# ESC-simple_V2A.net
KiCad netlist of a schematic drawn in EAGLE
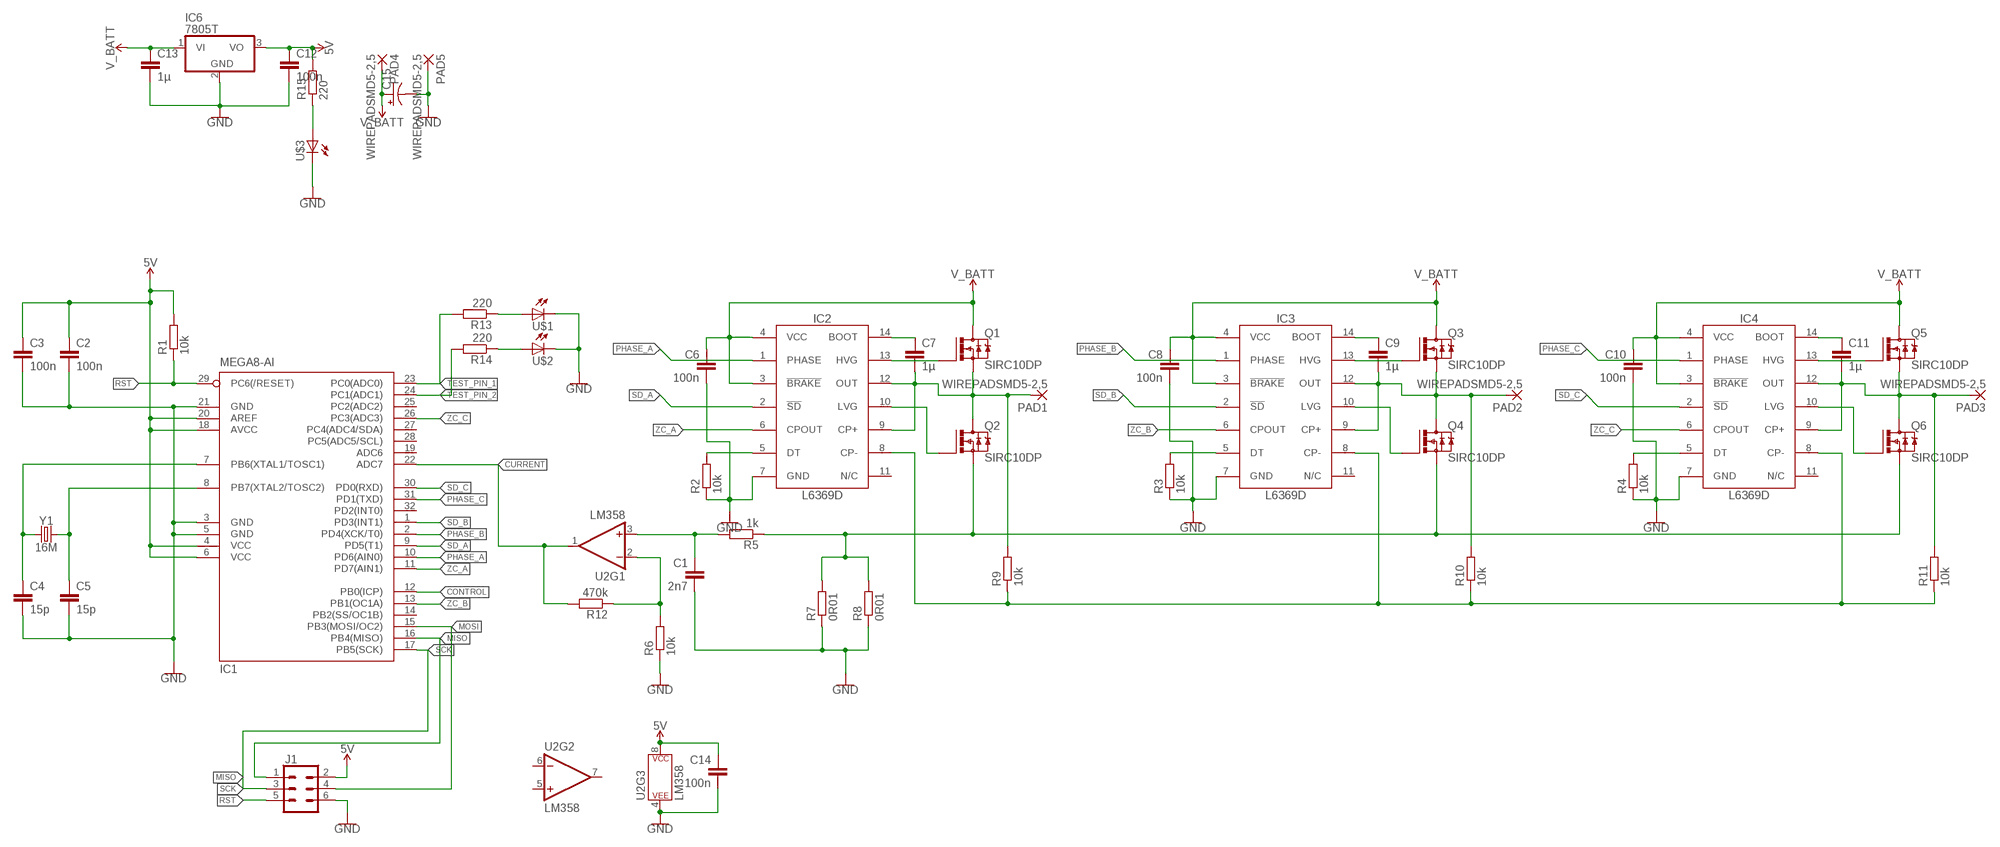
[diagram p0: schematic, sheet 1]

(export (version "E")
  (design (tool "Eeschema 10.0.6"))
  (components
    (comp (ref "C1")
      (value "2n7")
      (footprint "eagle-import:C1206K")
      (libsource (lib "eagle-import") (part "C-EUC1206K"))
    )
    (comp (ref "C2")
      (value "100n")
      (footprint "eagle-import:C1206K")
      (libsource (lib "eagle-import") (part "C-EUC1206K"))
    )
    (comp (ref "C3")
      (value "100n")
      (footprint "eagle-import:C1206K")
      (libsource (lib "eagle-import") (part "C-EUC1206K"))
    )
    (comp (ref "C4")
      (value "15p")
      (footprint "eagle-import:C1206K")
      (libsource (lib "eagle-import") (part "C-EUC1206K"))
    )
    (comp (ref "C5")
      (value "15p")
      (footprint "eagle-import:C1206K")
      (libsource (lib "eagle-import") (part "C-EUC1206K"))
    )
    (comp (ref "C6")
      (value "100n")
      (footprint "eagle-import:C1206K")
      (libsource (lib "eagle-import") (part "C-EUC1206K"))
    )
    (comp (ref "C7")
      (value "1µ")
      (footprint "eagle-import:C1206K")
      (libsource (lib "eagle-import") (part "C-EUC1206K"))
    )
    (comp (ref "C8")
      (value "100n")
      (footprint "eagle-import:C1206K")
      (libsource (lib "eagle-import") (part "C-EUC1206K"))
    )
    (comp (ref "C9")
      (value "1µ")
      (footprint "eagle-import:C1206K")
      (libsource (lib "eagle-import") (part "C-EUC1206K"))
    )
    (comp (ref "C10")
      (value "100n")
      (footprint "eagle-import:C1206K")
      (libsource (lib "eagle-import") (part "C-EUC1206K"))
    )
    (comp (ref "C11")
      (value "1µ")
      (footprint "eagle-import:C1206K")
      (libsource (lib "eagle-import") (part "C-EUC1206K"))
    )
    (comp (ref "C12")
      (value "100n")
      (footprint "eagle-import:C1206K")
      (libsource (lib "eagle-import") (part "C-EUC1206K"))
    )
    (comp (ref "C13")
      (value "1µ")
      (footprint "eagle-import:C1206K")
      (libsource (lib "eagle-import") (part "C-EUC1206K"))
    )
    (comp (ref "C14")
      (value "100n")
      (footprint "eagle-import:C1206K")
      (libsource (lib "eagle-import") (part "C-EUC1206K"))
    )
    (comp (ref "C15")
      (value "CPOL-USE5-13")
      (footprint "eagle-import:E5-13")
      (libsource (lib "eagle-import") (part "CPOL-USE5-13"))
    )
    (comp (ref "IC1")
      (value "MEGA8-AI")
      (footprint "eagle-import:TQFP32-08")
      (fields (field (name "MPN") "ATMEGA8-16AU"))
      (libsource (lib "eagle-import") (part "MEGA8-AI"))
    )
    (comp (ref "IC2")
      (value "L6369D")
      (footprint "eagle-import:SO-14")
      (libsource (lib "eagle-import") (part "L6369D"))
    )
    (comp (ref "IC3")
      (value "L6369D")
      (footprint "eagle-import:SO-14")
      (libsource (lib "eagle-import") (part "L6369D"))
    )
    (comp (ref "IC4")
      (value "L6369D")
      (footprint "eagle-import:SO-14")
      (libsource (lib "eagle-import") (part "L6369D"))
    )
    (comp (ref "IC6")
      (value "7805T")
      (footprint "eagle-import:TO220H")
      (libsource (lib "eagle-import") (part "78T05"))
    )
    (comp (ref "J1")
      (value "CONN_03X22X3_SILK_MALE_PTH")
      (footprint "eagle-import:2X3")
      (libsource (lib "eagle-import") (part "CONN_03X22X3_SILK_MALE_PTH"))
    )
    (comp (ref "PAD1")
      (value "WIREPADSMD5-2,5")
      (footprint "eagle-import:5-2,5")
      (libsource (lib "eagle-import") (part "WIREPADSMD5-2,5"))
    )
    (comp (ref "PAD2")
      (value "WIREPADSMD5-2,5")
      (footprint "eagle-import:5-2,5")
      (libsource (lib "eagle-import") (part "WIREPADSMD5-2,5"))
    )
    (comp (ref "PAD3")
      (value "WIREPADSMD5-2,5")
      (footprint "eagle-import:5-2,5")
      (libsource (lib "eagle-import") (part "WIREPADSMD5-2,5"))
    )
    (comp (ref "PAD4")
      (value "WIREPADSMD5-2,5")
      (footprint "eagle-import:5-2,5")
      (libsource (lib "eagle-import") (part "WIREPADSMD5-2,5"))
    )
    (comp (ref "PAD5")
      (value "WIREPADSMD5-2,5")
      (footprint "eagle-import:5-2,5")
      (libsource (lib "eagle-import") (part "WIREPADSMD5-2,5"))
    )
    (comp (ref "Q1")
      (value "SIRC10DP")
      (footprint "eagle-import:POWERPAK_SO-8_SINGLE")
      (libsource (lib "eagle-import") (part "SIRC10DP"))
    )
    (comp (ref "Q2")
      (value "SIRC10DP")
      (footprint "eagle-import:POWERPAK_SO-8_SINGLE")
      (libsource (lib "eagle-import") (part "SIRC10DP"))
    )
    (comp (ref "Q3")
      (value "SIRC10DP")
      (footprint "eagle-import:POWERPAK_SO-8_SINGLE")
      (libsource (lib "eagle-import") (part "SIRC10DP"))
    )
    (comp (ref "Q4")
      (value "SIRC10DP")
      (footprint "eagle-import:POWERPAK_SO-8_SINGLE")
      (libsource (lib "eagle-import") (part "SIRC10DP"))
    )
    (comp (ref "Q5")
      (value "SIRC10DP")
      (footprint "eagle-import:POWERPAK_SO-8_SINGLE")
      (libsource (lib "eagle-import") (part "SIRC10DP"))
    )
    (comp (ref "Q6")
      (value "SIRC10DP")
      (footprint "eagle-import:POWERPAK_SO-8_SINGLE")
      (libsource (lib "eagle-import") (part "SIRC10DP"))
    )
    (comp (ref "R1")
      (value "10k")
      (footprint "eagle-import:R1206")
      (libsource (lib "eagle-import") (part "R-EU_R1206"))
    )
    (comp (ref "R2")
      (value "10k")
      (footprint "eagle-import:R1206")
      (libsource (lib "eagle-import") (part "R-EU_R1206"))
    )
    (comp (ref "R3")
      (value "10k")
      (footprint "eagle-import:R1206")
      (libsource (lib "eagle-import") (part "R-EU_R1206"))
    )
    (comp (ref "R4")
      (value "10k")
      (footprint "eagle-import:R1206")
      (libsource (lib "eagle-import") (part "R-EU_R1206"))
    )
    (comp (ref "R5")
      (value "1k")
      (footprint "eagle-import:R1206")
      (libsource (lib "eagle-import") (part "R-EU_R1206"))
    )
    (comp (ref "R6")
      (value "10k")
      (footprint "eagle-import:R1206")
      (libsource (lib "eagle-import") (part "R-EU_R1206"))
    )
    (comp (ref "R7")
      (value "0R01")
      (footprint "eagle-import:R1206")
      (libsource (lib "eagle-import") (part "R-EU_R1206"))
    )
    (comp (ref "R8")
      (value "0R01")
      (footprint "eagle-import:R1206")
      (libsource (lib "eagle-import") (part "R-EU_R1206"))
    )
    (comp (ref "R9")
      (value "10k")
      (footprint "eagle-import:R1206")
      (libsource (lib "eagle-import") (part "R-EU_R1206"))
    )
    (comp (ref "R10")
      (value "10k")
      (footprint "eagle-import:R1206")
      (libsource (lib "eagle-import") (part "R-EU_R1206"))
    )
    (comp (ref "R11")
      (value "10k")
      (footprint "eagle-import:R1206")
      (libsource (lib "eagle-import") (part "R-EU_R1206"))
    )
    (comp (ref "R12")
      (value "470k")
      (footprint "eagle-import:R1206")
      (libsource (lib "eagle-import") (part "R-EU_R1206"))
    )
    (comp (ref "R13")
      (value "220")
      (footprint "eagle-import:R1206")
      (libsource (lib "eagle-import") (part "R-EU_R1206"))
    )
    (comp (ref "R14")
      (value "220")
      (footprint "eagle-import:R1206")
      (libsource (lib "eagle-import") (part "R-EU_R1206"))
    )
    (comp (ref "R15")
      (value "220")
      (footprint "eagle-import:R1206")
      (libsource (lib "eagle-import") (part "R-EU_R1206"))
    )
    (comp (ref "U$1")
      (value "LED")
      (footprint "eagle-import:3MM_LED")
      (libsource (lib "eagle-import") (part "LED"))
    )
    (comp (ref "U$2")
      (value "LED")
      (footprint "eagle-import:3MM_LED")
      (libsource (lib "eagle-import") (part "LED"))
    )
    (comp (ref "U$3")
      (value "LED")
      (footprint "eagle-import:3MM_LED")
      (libsource (lib "eagle-import") (part "LED"))
    )
    (comp (ref "U2")
      (value "LM358")
      (footprint "eagle-import:DIP08")
      (libsource (lib "eagle-import") (part "LM358"))
    )
    (comp (ref "Y1")
      (value "16M")
      (footprint "eagle-import:HC49UP")
      (libsource (lib "eagle-import") (part "CRYSTALSMD-HC49UP"))
    )
  )
  (nets
    (net (code "1") (name "5V") (class "Default")
      (node (ref "C12") (pin "1") (pinfunction "1_1") (pintype "passive"))
      (node (ref "C14") (pin "1") (pinfunction "1_1") (pintype "passive"))
      (node (ref "C2") (pin "1") (pinfunction "1_1") (pintype "passive"))
      (node (ref "C3") (pin "1") (pinfunction "1_1") (pintype "passive"))
      (node (ref "IC1") (pin "18") (pinfunction "AVCC_18") (pintype "power_in"))
      (node (ref "IC1") (pin "20") (pinfunction "AREF_20") (pintype "passive"))
      (node (ref "IC1") (pin "4") (pinfunction "VCC_4") (pintype "power_in"))
      (node (ref "IC1") (pin "6") (pinfunction "VCC_6") (pintype "power_in"))
      (node (ref "IC6") (pin "3") (pinfunction "VO_3") (pintype "passive"))
      (node (ref "J1") (pin "2") (pinfunction "2_2") (pintype "bidirectional"))
      (node (ref "R1") (pin "2") (pinfunction "2_2") (pintype "passive"))
      (node (ref "R15") (pin "2") (pinfunction "2_2") (pintype "passive"))
      (node (ref "U2") (pin "8") (pinfunction "P$V+_8") (pintype "bidirectional"))
    )
    (net (code "2") (name "CONTROL") (class "Default")
      (node (ref "IC1") (pin "12") (pinfunction "PB0(ICP)_12") (pintype "bidirectional"))
    )
    (net (code "3") (name "CURRENT") (class "Default")
      (node (ref "IC1") (pin "22") (pinfunction "ADC7_22") (pintype "bidirectional"))
      (node (ref "R12") (pin "2") (pinfunction "2_2") (pintype "passive"))
      (node (ref "U2") (pin "1") (pinfunction "OUT_1") (pintype "output"))
    )
    (net (code "4") (name "GND") (class "Default")
      (node (ref "C1") (pin "2") (pinfunction "2_2") (pintype "passive"))
      (node (ref "C10") (pin "2") (pinfunction "2_2") (pintype "passive"))
      (node (ref "C12") (pin "2") (pinfunction "2_2") (pintype "passive"))
      (node (ref "C13") (pin "2") (pinfunction "2_2") (pintype "passive"))
      (node (ref "C14") (pin "2") (pinfunction "2_2") (pintype "passive"))
      (node (ref "C15") (pin "-") (pinfunction "-_-") (pintype "passive"))
      (node (ref "C2") (pin "2") (pinfunction "2_2") (pintype "passive"))
      (node (ref "C3") (pin "2") (pinfunction "2_2") (pintype "passive"))
      (node (ref "C4") (pin "2") (pinfunction "2_2") (pintype "passive"))
      (node (ref "C5") (pin "2") (pinfunction "2_2") (pintype "passive"))
      (node (ref "C6") (pin "2") (pinfunction "2_2") (pintype "passive"))
      (node (ref "C8") (pin "2") (pinfunction "2_2") (pintype "passive"))
      (node (ref "IC1") (pin "21") (pinfunction "GND_21") (pintype "power_in"))
      (node (ref "IC1") (pin "3") (pinfunction "GND_3") (pintype "power_in"))
      (node (ref "IC1") (pin "5") (pinfunction "GND_5") (pintype "power_in"))
      (node (ref "IC2") (pin "7") (pinfunction "GND_7") (pintype "power_in"))
      (node (ref "IC3") (pin "7") (pinfunction "GND_7") (pintype "power_in"))
      (node (ref "IC4") (pin "7") (pinfunction "GND_7") (pintype "power_in"))
      (node (ref "IC6") (pin "2") (pinfunction "GND_2") (pintype "passive"))
      (node (ref "J1") (pin "6") (pinfunction "6_6") (pintype "bidirectional"))
      (node (ref "PAD5") (pin "1") (pinfunction "P_1") (pintype "passive"))
      (node (ref "R2") (pin "1") (pinfunction "1_1") (pintype "passive"))
      (node (ref "R3") (pin "1") (pinfunction "1_1") (pintype "passive"))
      (node (ref "R4") (pin "1") (pinfunction "1_1") (pintype "passive"))
      (node (ref "R6") (pin "1") (pinfunction "1_1") (pintype "passive"))
      (node (ref "R7") (pin "1") (pinfunction "1_1") (pintype "passive"))
      (node (ref "R8") (pin "1") (pinfunction "1_1") (pintype "passive"))
      (node (ref "U$1") (pin "C") (pinfunction "C_C") (pintype "passive"))
      (node (ref "U$2") (pin "C") (pinfunction "C_C") (pintype "passive"))
      (node (ref "U$3") (pin "C") (pinfunction "C_C") (pintype "passive"))
      (node (ref "U2") (pin "4") (pinfunction "P$V-_4") (pintype "bidirectional"))
    )
    (net (code "5") (name "MISO") (class "Default")
      (node (ref "IC1") (pin "16") (pinfunction "PB4(MISO)_16") (pintype "bidirectional"))
      (node (ref "J1") (pin "1") (pinfunction "1_1") (pintype "bidirectional"))
    )
    (net (code "6") (name "MOSI") (class "Default")
      (node (ref "IC1") (pin "15") (pinfunction "PB3(MOSI/OC2)_15") (pintype "bidirectional"))
      (node (ref "J1") (pin "4") (pinfunction "4_4") (pintype "bidirectional"))
    )
    (net (code "7") (name "Net-(IC1-PB6(XTAL1{slash}TOSC1))") (class "Default")
      (node (ref "C4") (pin "1") (pinfunction "1_1") (pintype "passive"))
      (node (ref "IC1") (pin "7") (pinfunction "PB6(XTAL1/TOSC1)_7") (pintype "bidirectional"))
      (node (ref "Y1") (pin "1") (pinfunction "1_1") (pintype "passive"))
    )
    (net (code "8") (name "Net-(IC1-PB7(XTAL2{slash}TOSC2))") (class "Default")
      (node (ref "C5") (pin "1") (pinfunction "1_1") (pintype "passive"))
      (node (ref "IC1") (pin "8") (pinfunction "PB7(XTAL2/TOSC2)_8") (pintype "bidirectional"))
      (node (ref "Y1") (pin "2") (pinfunction "2_2") (pintype "passive"))
    )
    (net (code "9") (name "Net-(IC2-BOOT)") (class "Default")
      (node (ref "C7") (pin "1") (pinfunction "1_1") (pintype "passive"))
      (node (ref "IC2") (pin "14") (pinfunction "BOOT_14") (pintype "power_in"))
    )
    (net (code "10") (name "Net-(IC2-CP+)") (class "Default")
      (node (ref "C7") (pin "2") (pinfunction "2_2") (pintype "passive"))
      (node (ref "IC2") (pin "12") (pinfunction "OUT_12") (pintype "output"))
      (node (ref "IC2") (pin "9") (pinfunction "CP+_9") (pintype "input"))
      (node (ref "PAD1") (pin "1") (pinfunction "P_1") (pintype "passive"))
      (node (ref "Q1") (pin "1") (pinfunction "S_1") (pintype "bidirectional"))
      (node (ref "Q1") (pin "2") (pinfunction "S_2") (pintype "bidirectional"))
      (node (ref "Q1") (pin "3") (pinfunction "S_3") (pintype "bidirectional"))
      (node (ref "Q2") (pin "5") (pinfunction "D_5") (pintype "bidirectional"))
      (node (ref "Q2") (pin "6") (pinfunction "D_6") (pintype "bidirectional"))
      (node (ref "Q2") (pin "7") (pinfunction "D_7") (pintype "bidirectional"))
      (node (ref "Q2") (pin "8") (pinfunction "D_8") (pintype "bidirectional"))
      (node (ref "Q2") (pin "9") (pinfunction "D_9") (pintype "bidirectional"))
      (node (ref "R9") (pin "2") (pinfunction "2_2") (pintype "passive"))
    )
    (net (code "11") (name "Net-(IC2-CP-)") (class "Default")
      (node (ref "IC2") (pin "8") (pinfunction "CP-_8") (pintype "input"))
      (node (ref "IC3") (pin "8") (pinfunction "CP-_8") (pintype "input"))
      (node (ref "IC4") (pin "8") (pinfunction "CP-_8") (pintype "input"))
      (node (ref "R10") (pin "1") (pinfunction "1_1") (pintype "passive"))
      (node (ref "R11") (pin "1") (pinfunction "1_1") (pintype "passive"))
      (node (ref "R9") (pin "1") (pinfunction "1_1") (pintype "passive"))
    )
    (net (code "12") (name "Net-(IC2-DT)") (class "Default")
      (node (ref "IC2") (pin "5") (pinfunction "DT_5") (pintype "input"))
      (node (ref "R2") (pin "2") (pinfunction "2_2") (pintype "passive"))
    )
    (net (code "13") (name "Net-(IC2-HVG)") (class "Default")
      (node (ref "IC2") (pin "13") (pinfunction "HVG_13") (pintype "output"))
      (node (ref "Q1") (pin "4") (pinfunction "G_4") (pintype "bidirectional"))
    )
    (net (code "14") (name "Net-(IC2-LVG)") (class "Default")
      (node (ref "IC2") (pin "10") (pinfunction "LVG_10") (pintype "output"))
      (node (ref "Q2") (pin "4") (pinfunction "G_4") (pintype "bidirectional"))
    )
    (net (code "15") (name "Net-(IC3-BOOT)") (class "Default")
      (node (ref "C9") (pin "1") (pinfunction "1_1") (pintype "passive"))
      (node (ref "IC3") (pin "14") (pinfunction "BOOT_14") (pintype "power_in"))
    )
    (net (code "16") (name "Net-(IC3-CP+)") (class "Default")
      (node (ref "C9") (pin "2") (pinfunction "2_2") (pintype "passive"))
      (node (ref "IC3") (pin "12") (pinfunction "OUT_12") (pintype "output"))
      (node (ref "IC3") (pin "9") (pinfunction "CP+_9") (pintype "input"))
      (node (ref "PAD2") (pin "1") (pinfunction "P_1") (pintype "passive"))
      (node (ref "Q3") (pin "1") (pinfunction "S_1") (pintype "bidirectional"))
      (node (ref "Q3") (pin "2") (pinfunction "S_2") (pintype "bidirectional"))
      (node (ref "Q3") (pin "3") (pinfunction "S_3") (pintype "bidirectional"))
      (node (ref "Q4") (pin "5") (pinfunction "D_5") (pintype "bidirectional"))
      (node (ref "Q4") (pin "6") (pinfunction "D_6") (pintype "bidirectional"))
      (node (ref "Q4") (pin "7") (pinfunction "D_7") (pintype "bidirectional"))
      (node (ref "Q4") (pin "8") (pinfunction "D_8") (pintype "bidirectional"))
      (node (ref "Q4") (pin "9") (pinfunction "D_9") (pintype "bidirectional"))
      (node (ref "R10") (pin "2") (pinfunction "2_2") (pintype "passive"))
    )
    (net (code "17") (name "Net-(IC3-DT)") (class "Default")
      (node (ref "IC3") (pin "5") (pinfunction "DT_5") (pintype "input"))
      (node (ref "R3") (pin "2") (pinfunction "2_2") (pintype "passive"))
    )
    (net (code "18") (name "Net-(IC3-HVG)") (class "Default")
      (node (ref "IC3") (pin "13") (pinfunction "HVG_13") (pintype "output"))
      (node (ref "Q3") (pin "4") (pinfunction "G_4") (pintype "bidirectional"))
    )
    (net (code "19") (name "Net-(IC3-LVG)") (class "Default")
      (node (ref "IC3") (pin "10") (pinfunction "LVG_10") (pintype "output"))
      (node (ref "Q4") (pin "4") (pinfunction "G_4") (pintype "bidirectional"))
    )
    (net (code "20") (name "Net-(IC4-BOOT)") (class "Default")
      (node (ref "C11") (pin "1") (pinfunction "1_1") (pintype "passive"))
      (node (ref "IC4") (pin "14") (pinfunction "BOOT_14") (pintype "power_in"))
    )
    (net (code "21") (name "Net-(IC4-CP+)") (class "Default")
      (node (ref "C11") (pin "2") (pinfunction "2_2") (pintype "passive"))
      (node (ref "IC4") (pin "12") (pinfunction "OUT_12") (pintype "output"))
      (node (ref "IC4") (pin "9") (pinfunction "CP+_9") (pintype "input"))
      (node (ref "PAD3") (pin "1") (pinfunction "P_1") (pintype "passive"))
      (node (ref "Q5") (pin "1") (pinfunction "S_1") (pintype "bidirectional"))
      (node (ref "Q5") (pin "2") (pinfunction "S_2") (pintype "bidirectional"))
      (node (ref "Q5") (pin "3") (pinfunction "S_3") (pintype "bidirectional"))
      (node (ref "Q6") (pin "5") (pinfunction "D_5") (pintype "bidirectional"))
      (node (ref "Q6") (pin "6") (pinfunction "D_6") (pintype "bidirectional"))
      (node (ref "Q6") (pin "7") (pinfunction "D_7") (pintype "bidirectional"))
      (node (ref "Q6") (pin "8") (pinfunction "D_8") (pintype "bidirectional"))
      (node (ref "Q6") (pin "9") (pinfunction "D_9") (pintype "bidirectional"))
      (node (ref "R11") (pin "2") (pinfunction "2_2") (pintype "passive"))
    )
    (net (code "22") (name "Net-(IC4-DT)") (class "Default")
      (node (ref "IC4") (pin "5") (pinfunction "DT_5") (pintype "input"))
      (node (ref "R4") (pin "2") (pinfunction "2_2") (pintype "passive"))
    )
    (net (code "23") (name "Net-(IC4-HVG)") (class "Default")
      (node (ref "IC4") (pin "13") (pinfunction "HVG_13") (pintype "output"))
      (node (ref "Q5") (pin "4") (pinfunction "G_4") (pintype "bidirectional"))
    )
    (net (code "24") (name "Net-(IC4-LVG)") (class "Default")
      (node (ref "IC4") (pin "10") (pinfunction "LVG_10") (pintype "output"))
      (node (ref "Q6") (pin "4") (pinfunction "G_4") (pintype "bidirectional"))
    )
    (net (code "25") (name "Net-(Q2-S-Pad1)") (class "Default")
      (node (ref "Q2") (pin "1") (pinfunction "S_1") (pintype "bidirectional"))
      (node (ref "Q2") (pin "2") (pinfunction "S_2") (pintype "bidirectional"))
      (node (ref "Q2") (pin "3") (pinfunction "S_3") (pintype "bidirectional"))
      (node (ref "Q4") (pin "1") (pinfunction "S_1") (pintype "bidirectional"))
      (node (ref "Q4") (pin "2") (pinfunction "S_2") (pintype "bidirectional"))
      (node (ref "Q4") (pin "3") (pinfunction "S_3") (pintype "bidirectional"))
      (node (ref "Q6") (pin "1") (pinfunction "S_1") (pintype "bidirectional"))
      (node (ref "Q6") (pin "2") (pinfunction "S_2") (pintype "bidirectional"))
      (node (ref "Q6") (pin "3") (pinfunction "S_3") (pintype "bidirectional"))
      (node (ref "R5") (pin "1") (pinfunction "1_1") (pintype "passive"))
      (node (ref "R7") (pin "2") (pinfunction "2_2") (pintype "passive"))
      (node (ref "R8") (pin "2") (pinfunction "2_2") (pintype "passive"))
    )
    (net (code "26") (name "Net-(R13-Pad1)") (class "Default")
      (node (ref "R13") (pin "1") (pinfunction "1_1") (pintype "passive"))
      (node (ref "U$1") (pin "A") (pinfunction "A_A") (pintype "passive"))
    )
    (net (code "27") (name "Net-(R14-Pad1)") (class "Default")
      (node (ref "R14") (pin "1") (pinfunction "1_1") (pintype "passive"))
      (node (ref "U$2") (pin "A") (pinfunction "A_A") (pintype "passive"))
    )
    (net (code "28") (name "Net-(R15-Pad1)") (class "Default")
      (node (ref "R15") (pin "1") (pinfunction "1_1") (pintype "passive"))
      (node (ref "U$3") (pin "A") (pinfunction "A_A") (pintype "passive"))
    )
    (net (code "29") (name "Net-(U2A-+IN)") (class "Default")
      (node (ref "C1") (pin "1") (pinfunction "1_1") (pintype "passive"))
      (node (ref "R5") (pin "2") (pinfunction "2_2") (pintype "passive"))
      (node (ref "U2") (pin "3") (pinfunction "+IN_3") (pintype "input"))
    )
    (net (code "30") (name "Net-(U2A--IN)") (class "Default")
      (node (ref "R12") (pin "1") (pinfunction "1_1") (pintype "passive"))
      (node (ref "R6") (pin "2") (pinfunction "2_2") (pintype "passive"))
      (node (ref "U2") (pin "2") (pinfunction "-IN_2") (pintype "input"))
    )
    (net (code "31") (name "PHASE_A") (class "Default")
      (node (ref "IC1") (pin "10") (pinfunction "PD6(AIN0)_10") (pintype "bidirectional"))
      (node (ref "IC2") (pin "1") (pinfunction "PHASE_1") (pintype "input"))
    )
    (net (code "32") (name "PHASE_B") (class "Default")
      (node (ref "IC1") (pin "2") (pinfunction "PD4(XCK/T0)_2") (pintype "bidirectional"))
      (node (ref "IC3") (pin "1") (pinfunction "PHASE_1") (pintype "input"))
    )
    (net (code "33") (name "PHASE_C") (class "Default")
      (node (ref "IC1") (pin "31") (pinfunction "PD1(TXD)_31") (pintype "bidirectional"))
      (node (ref "IC4") (pin "1") (pinfunction "PHASE_1") (pintype "input"))
    )
    (net (code "34") (name "RST") (class "Default")
      (node (ref "IC1") (pin "29") (pinfunction "PC6(/RESET)_29") (pintype "bidirectional"))
      (node (ref "J1") (pin "5") (pinfunction "5_5") (pintype "bidirectional"))
      (node (ref "R1") (pin "1") (pinfunction "1_1") (pintype "passive"))
    )
    (net (code "35") (name "SCK") (class "Default")
      (node (ref "IC1") (pin "17") (pinfunction "PB5(SCK)_17") (pintype "bidirectional"))
      (node (ref "J1") (pin "3") (pinfunction "3_3") (pintype "bidirectional"))
    )
    (net (code "36") (name "SD_A") (class "Default")
      (node (ref "IC1") (pin "9") (pinfunction "PD5(T1)_9") (pintype "bidirectional"))
      (node (ref "IC2") (pin "2") (pinfunction "~{SD}_2") (pintype "input"))
    )
    (net (code "37") (name "SD_B") (class "Default")
      (node (ref "IC1") (pin "1") (pinfunction "PD3(INT1)_1") (pintype "bidirectional"))
      (node (ref "IC3") (pin "2") (pinfunction "~{SD}_2") (pintype "input"))
    )
    (net (code "38") (name "SD_C") (class "Default")
      (node (ref "IC1") (pin "30") (pinfunction "PD0(RXD)_30") (pintype "bidirectional"))
      (node (ref "IC4") (pin "2") (pinfunction "~{SD}_2") (pintype "input"))
    )
    (net (code "39") (name "TEST_PIN_1") (class "Default")
      (node (ref "IC1") (pin "23") (pinfunction "PC0(ADC0)_23") (pintype "bidirectional"))
      (node (ref "R13") (pin "2") (pinfunction "2_2") (pintype "passive"))
    )
    (net (code "40") (name "TEST_PIN_2") (class "Default")
      (node (ref "IC1") (pin "24") (pinfunction "PC1(ADC1)_24") (pintype "bidirectional"))
      (node (ref "R14") (pin "2") (pinfunction "2_2") (pintype "passive"))
    )
    (net (code "41") (name "V_BATT") (class "Default")
      (node (ref "C10") (pin "1") (pinfunction "1_1") (pintype "passive"))
      (node (ref "C13") (pin "1") (pinfunction "1_1") (pintype "passive"))
      (node (ref "C15") (pin "+") (pinfunction "+_+") (pintype "passive"))
      (node (ref "C6") (pin "1") (pinfunction "1_1") (pintype "passive"))
      (node (ref "C8") (pin "1") (pinfunction "1_1") (pintype "passive"))
      (node (ref "IC2") (pin "3") (pinfunction "~{BRAKE}_3") (pintype "input"))
      (node (ref "IC2") (pin "4") (pinfunction "VCC_4") (pintype "power_in"))
      (node (ref "IC3") (pin "3") (pinfunction "~{BRAKE}_3") (pintype "input"))
      (node (ref "IC3") (pin "4") (pinfunction "VCC_4") (pintype "power_in"))
      (node (ref "IC4") (pin "3") (pinfunction "~{BRAKE}_3") (pintype "input"))
      (node (ref "IC4") (pin "4") (pinfunction "VCC_4") (pintype "power_in"))
      (node (ref "IC6") (pin "1") (pinfunction "VI_1") (pintype "input"))
      (node (ref "PAD4") (pin "1") (pinfunction "P_1") (pintype "passive"))
      (node (ref "Q1") (pin "5") (pinfunction "D_5") (pintype "bidirectional"))
      (node (ref "Q1") (pin "6") (pinfunction "D_6") (pintype "bidirectional"))
      (node (ref "Q1") (pin "7") (pinfunction "D_7") (pintype "bidirectional"))
      (node (ref "Q1") (pin "8") (pinfunction "D_8") (pintype "bidirectional"))
      (node (ref "Q1") (pin "9") (pinfunction "D_9") (pintype "bidirectional"))
      (node (ref "Q3") (pin "5") (pinfunction "D_5") (pintype "bidirectional"))
      (node (ref "Q3") (pin "6") (pinfunction "D_6") (pintype "bidirectional"))
      (node (ref "Q3") (pin "7") (pinfunction "D_7") (pintype "bidirectional"))
      (node (ref "Q3") (pin "8") (pinfunction "D_8") (pintype "bidirectional"))
      (node (ref "Q3") (pin "9") (pinfunction "D_9") (pintype "bidirectional"))
      (node (ref "Q5") (pin "5") (pinfunction "D_5") (pintype "bidirectional"))
      (node (ref "Q5") (pin "6") (pinfunction "D_6") (pintype "bidirectional"))
      (node (ref "Q5") (pin "7") (pinfunction "D_7") (pintype "bidirectional"))
      (node (ref "Q5") (pin "8") (pinfunction "D_8") (pintype "bidirectional"))
      (node (ref "Q5") (pin "9") (pinfunction "D_9") (pintype "bidirectional"))
    )
    (net (code "42") (name "ZC_A") (class "Default")
      (node (ref "IC1") (pin "11") (pinfunction "PD7(AIN1)_11") (pintype "bidirectional"))
      (node (ref "IC2") (pin "6") (pinfunction "CPOUT_6") (pintype "output"))
    )
    (net (code "43") (name "ZC_B") (class "Default")
      (node (ref "IC1") (pin "13") (pinfunction "PB1(OC1A)_13") (pintype "bidirectional"))
      (node (ref "IC3") (pin "6") (pinfunction "CPOUT_6") (pintype "output"))
    )
    (net (code "44") (name "ZC_C") (class "Default")
      (node (ref "IC1") (pin "26") (pinfunction "PC3(ADC3)_26") (pintype "bidirectional"))
      (node (ref "IC4") (pin "6") (pinfunction "CPOUT_6") (pintype "output"))
    )
    (net (code "45") (name "unconnected-(IC1-ADC6-Pad19)") (class "Default")
      (node (ref "IC1") (pin "19") (pinfunction "ADC6_19") (pintype "bidirectional"))
    )
    (net (code "46") (name "unconnected-(IC1-PB2(SS{slash}OC1B)-Pad14)") (class "Default")
      (node (ref "IC1") (pin "14") (pinfunction "PB2(SS/OC1B)_14") (pintype "bidirectional"))
    )
    (net (code "47") (name "unconnected-(IC1-PC2(ADC2)-Pad25)") (class "Default")
      (node (ref "IC1") (pin "25") (pinfunction "PC2(ADC2)_25") (pintype "bidirectional"))
    )
    (net (code "48") (name "unconnected-(IC1-PC4(ADC4{slash}SDA)-Pad27)") (class "Default")
      (node (ref "IC1") (pin "27") (pinfunction "PC4(ADC4/SDA)_27") (pintype "bidirectional"))
    )
    (net (code "49") (name "unconnected-(IC1-PC5(ADC5{slash}SCL)-Pad28)") (class "Default")
      (node (ref "IC1") (pin "28") (pinfunction "PC5(ADC5/SCL)_28") (pintype "bidirectional"))
    )
    (net (code "50") (name "unconnected-(IC1-PD2(INT0)-Pad32)") (class "Default")
      (node (ref "IC1") (pin "32") (pinfunction "PD2(INT0)_32") (pintype "bidirectional"))
    )
    (net (code "51") (name "unconnected-(IC2-N{slash}C-Pad11)") (class "Default")
      (node (ref "IC2") (pin "11") (pinfunction "N/C_11") (pintype "no_connect"))
    )
    (net (code "52") (name "unconnected-(IC3-N{slash}C-Pad11)") (class "Default")
      (node (ref "IC3") (pin "11") (pinfunction "N/C_11") (pintype "no_connect"))
    )
    (net (code "53") (name "unconnected-(IC4-N{slash}C-Pad11)") (class "Default")
      (node (ref "IC4") (pin "11") (pinfunction "N/C_11") (pintype "no_connect"))
    )
    (net (code "54") (name "unconnected-(U2B-+IN-Pad5)") (class "Default")
      (node (ref "U2") (pin "5") (pinfunction "+IN_5") (pintype "input"))
    )
    (net (code "55") (name "unconnected-(U2B--IN-Pad6)") (class "Default")
      (node (ref "U2") (pin "6") (pinfunction "-IN_6") (pintype "input"))
    )
    (net (code "56") (name "unconnected-(U2B-OUT-Pad7)") (class "Default")
      (node (ref "U2") (pin "7") (pinfunction "OUT_7") (pintype "output"))
    )
  )
)
